# unicorder-mk-1_2-display.net
KiCad netlist of a schematic drawn in EAGLE
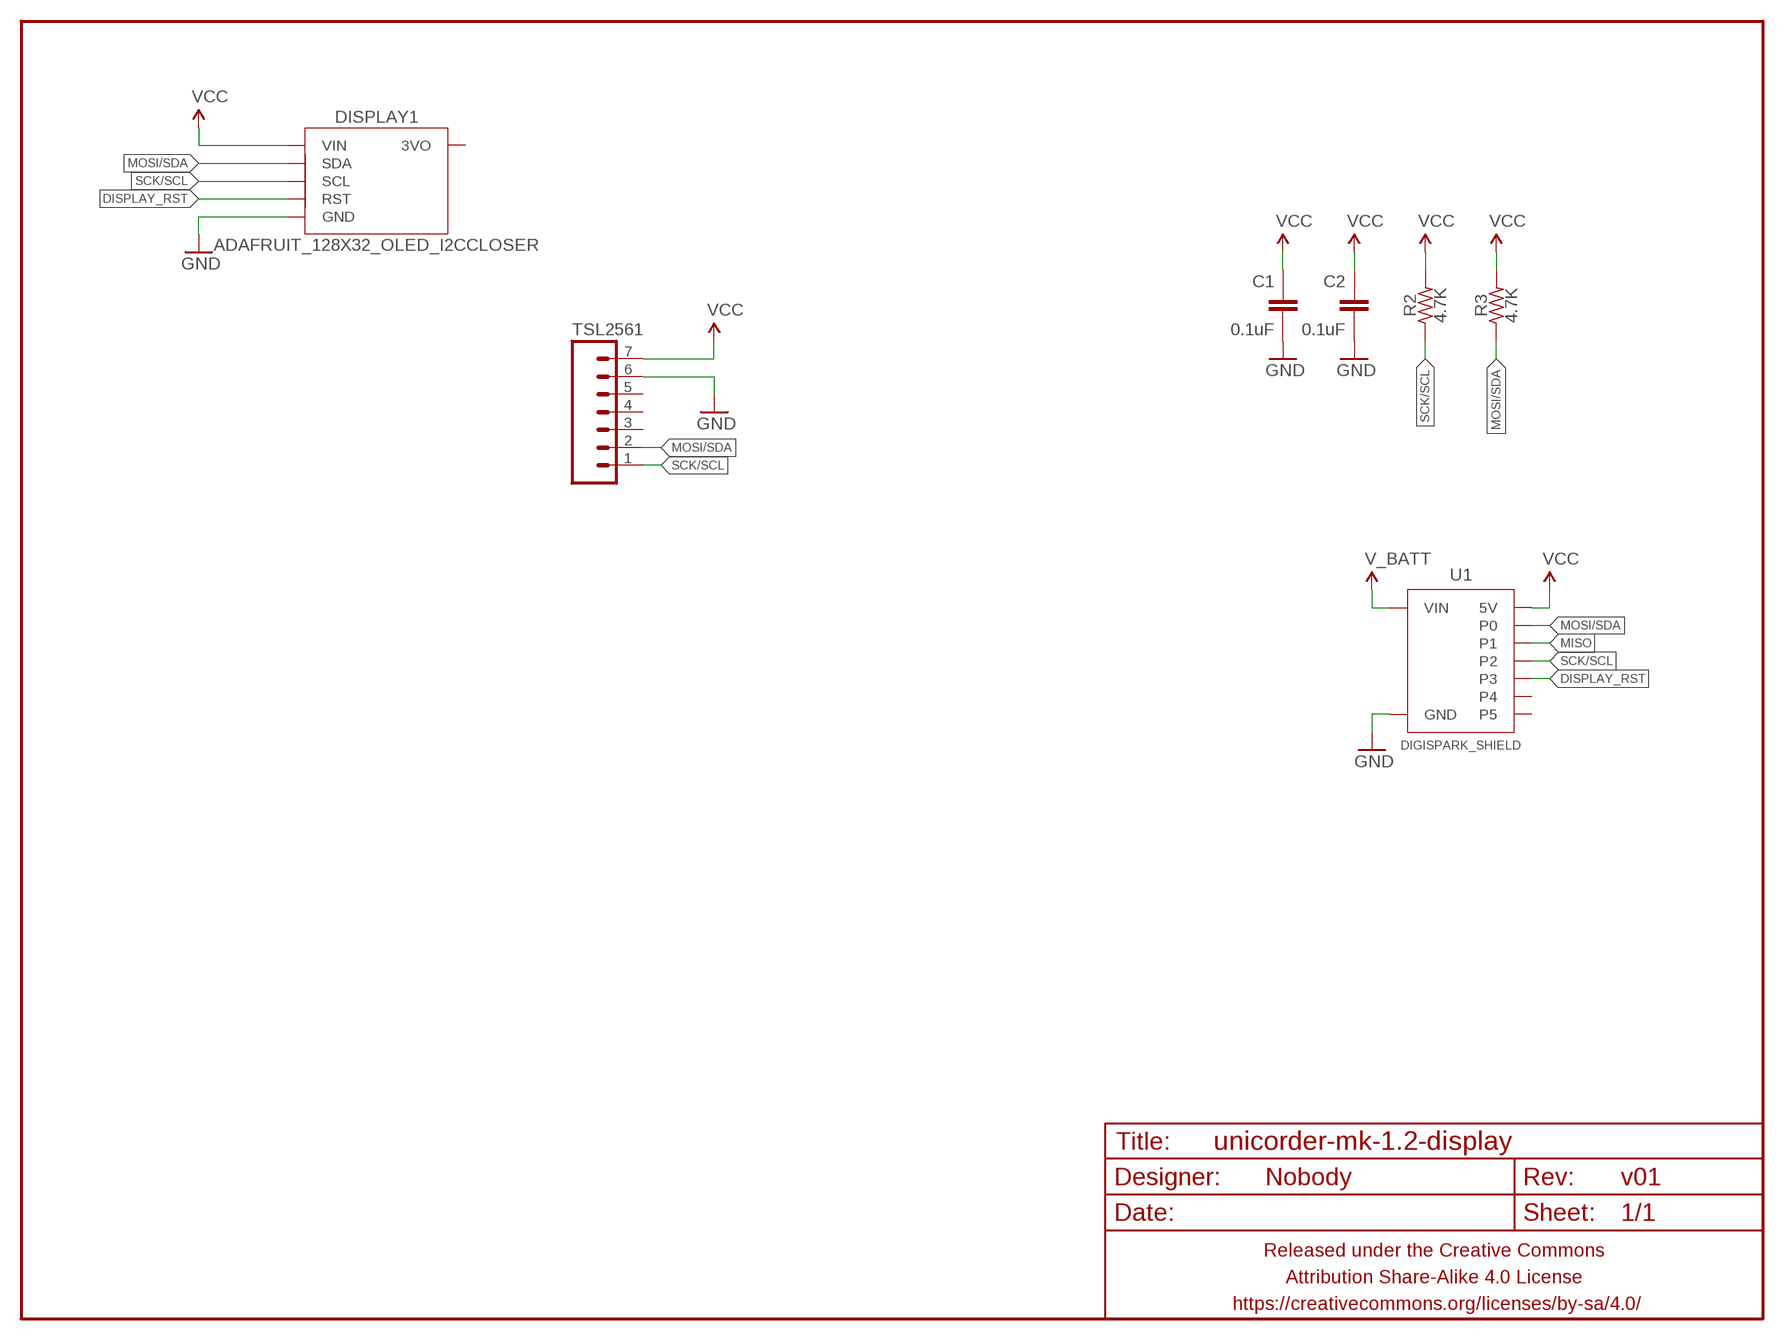
[diagram p0: schematic, sheet 1]

(export (version "E")
  (design (tool "Eeschema 10.0.6"))
  (components
    (comp (ref "C1")
      (value "0.1uF")
      (footprint "eagle-import:C025-024X044")
      (libsource (lib "eagle-import") (part "CAPACITOR-CERAMIC025-024X044"))
    )
    (comp (ref "C2")
      (value "0.1uF")
      (footprint "eagle-import:C025-024X044")
      (libsource (lib "eagle-import") (part "CAPACITOR-CERAMIC025-024X044"))
    )
    (comp (ref "DISPLAY1")
      (value "ADAFRUIT_128X32_OLED_I2CCLOSER")
      (footprint "eagle-import:ADAFRUIT_128X32_OLED_I2C_CLOSER")
      (libsource (lib "eagle-import") (part "ADAFRUIT_128X32_OLED_I2CCLOSER"))
    )
    (comp (ref "FRAME1")
      (value "FRAME-LETTERNO_PACKAGE")
      (footprint "eagle-import:DUMMY")
      (fields (field (name "DESIGNER") "Nobody"))
      (libsource (lib "eagle-import") (part "FRAME-LETTERNO_PACKAGE"))
    )
    (comp (ref "R2")
      (value "4.7K")
      (footprint "eagle-import:RESISTOR-AXIAL-PTH-7.62MM")
      (libsource (lib "eagle-import") (part "RESISTORPTH-AXIAL-7.62MM"))
    )
    (comp (ref "R3")
      (value "4.7K")
      (footprint "eagle-import:RESISTOR-AXIAL-PTH-7.62MM")
      (libsource (lib "eagle-import") (part "RESISTORPTH-AXIAL-7.62MM"))
    )
    (comp (ref "TSL2561")
      (value "M07PTH-SLIMASS")
      (footprint "eagle-import:1X07_PTH_SLIMASS")
      (libsource (lib "eagle-import") (part "M07PTH-SLIMASS"))
    )
    (comp (ref "U1")
      (value "DIGISPARK_SHIELD")
      (footprint "eagle-import:DIGISPARK_SHIELD")
      (libsource (lib "eagle-import") (part "DIGISPARK_SHIELD"))
    )
  )
  (nets
    (net (code "1") (name "DISPLAY_RST") (class "Default")
      (node (ref "DISPLAY1") (pin "RST") (pinfunction "RST_RST") (pintype "bidirectional"))
      (node (ref "U1") (pin "P3") (pinfunction "P3_P3") (pintype "bidirectional"))
    )
    (net (code "2") (name "GND") (class "Default")
      (node (ref "C1") (pin "2") (pinfunction "2_2") (pintype "passive"))
      (node (ref "C2") (pin "2") (pinfunction "2_2") (pintype "passive"))
      (node (ref "DISPLAY1") (pin "GND") (pinfunction "GND_GND") (pintype "bidirectional"))
      (node (ref "TSL2561") (pin "6") (pinfunction "6_6") (pintype "passive"))
      (node (ref "U1") (pin "GND") (pinfunction "GND_GND") (pintype "bidirectional"))
    )
    (net (code "3") (name "MISO") (class "Default")
      (node (ref "U1") (pin "P1") (pinfunction "P1_P1") (pintype "bidirectional"))
    )
    (net (code "4") (name "MOSI{slash}SDA") (class "Default")
      (node (ref "DISPLAY1") (pin "SDA") (pinfunction "SDA_SDA") (pintype "bidirectional"))
      (node (ref "R3") (pin "P$1") (pinfunction "1_P$1") (pintype "passive"))
      (node (ref "TSL2561") (pin "2") (pinfunction "2_2") (pintype "passive"))
      (node (ref "U1") (pin "P0") (pinfunction "P0_P0") (pintype "bidirectional"))
    )
    (net (code "5") (name "SCK{slash}SCL") (class "Default")
      (node (ref "DISPLAY1") (pin "SCL") (pinfunction "SCL_SCL") (pintype "bidirectional"))
      (node (ref "R2") (pin "P$1") (pinfunction "1_P$1") (pintype "passive"))
      (node (ref "TSL2561") (pin "1") (pinfunction "1_1") (pintype "passive"))
      (node (ref "U1") (pin "P2") (pinfunction "P2_P2") (pintype "bidirectional"))
    )
    (net (code "6") (name "VCC") (class "Default")
      (node (ref "C1") (pin "1") (pinfunction "1_1") (pintype "passive"))
      (node (ref "C2") (pin "1") (pinfunction "1_1") (pintype "passive"))
      (node (ref "DISPLAY1") (pin "VIN") (pinfunction "VIN_VIN") (pintype "bidirectional"))
      (node (ref "R2") (pin "P$2") (pinfunction "2_P$2") (pintype "passive"))
      (node (ref "R3") (pin "P$2") (pinfunction "2_P$2") (pintype "passive"))
      (node (ref "TSL2561") (pin "7") (pinfunction "7_7") (pintype "passive"))
      (node (ref "U1") (pin "5V") (pinfunction "5V_5V") (pintype "bidirectional"))
    )
    (net (code "7") (name "V_BATT") (class "Default")
      (node (ref "U1") (pin "VIN") (pinfunction "VIN_VIN") (pintype "bidirectional"))
    )
    (net (code "8") (name "unconnected-(DISPLAY1-Pad3VO)") (class "Default")
      (node (ref "DISPLAY1") (pin "3VO") (pinfunction "3VO_3VO") (pintype "bidirectional"))
    )
    (net (code "9") (name "unconnected-(TSL2561-Pad3)") (class "Default")
      (node (ref "TSL2561") (pin "3") (pinfunction "3_3") (pintype "passive"))
    )
    (net (code "10") (name "unconnected-(TSL2561-Pad4)") (class "Default")
      (node (ref "TSL2561") (pin "4") (pinfunction "4_4") (pintype "passive"))
    )
    (net (code "11") (name "unconnected-(TSL2561-Pad5)") (class "Default")
      (node (ref "TSL2561") (pin "5") (pinfunction "5_5") (pintype "passive"))
    )
    (net (code "12") (name "unconnected-(U1-PadP4)") (class "Default")
      (node (ref "U1") (pin "P4") (pinfunction "P4_P4") (pintype "bidirectional"))
    )
    (net (code "13") (name "unconnected-(U1-PadP5)") (class "Default")
      (node (ref "U1") (pin "P5") (pinfunction "P5_P5") (pintype "bidirectional"))
    )
  )
)
